# 2DD-17-mk-2_1.net
KiCad netlist of a schematic drawn in EAGLE
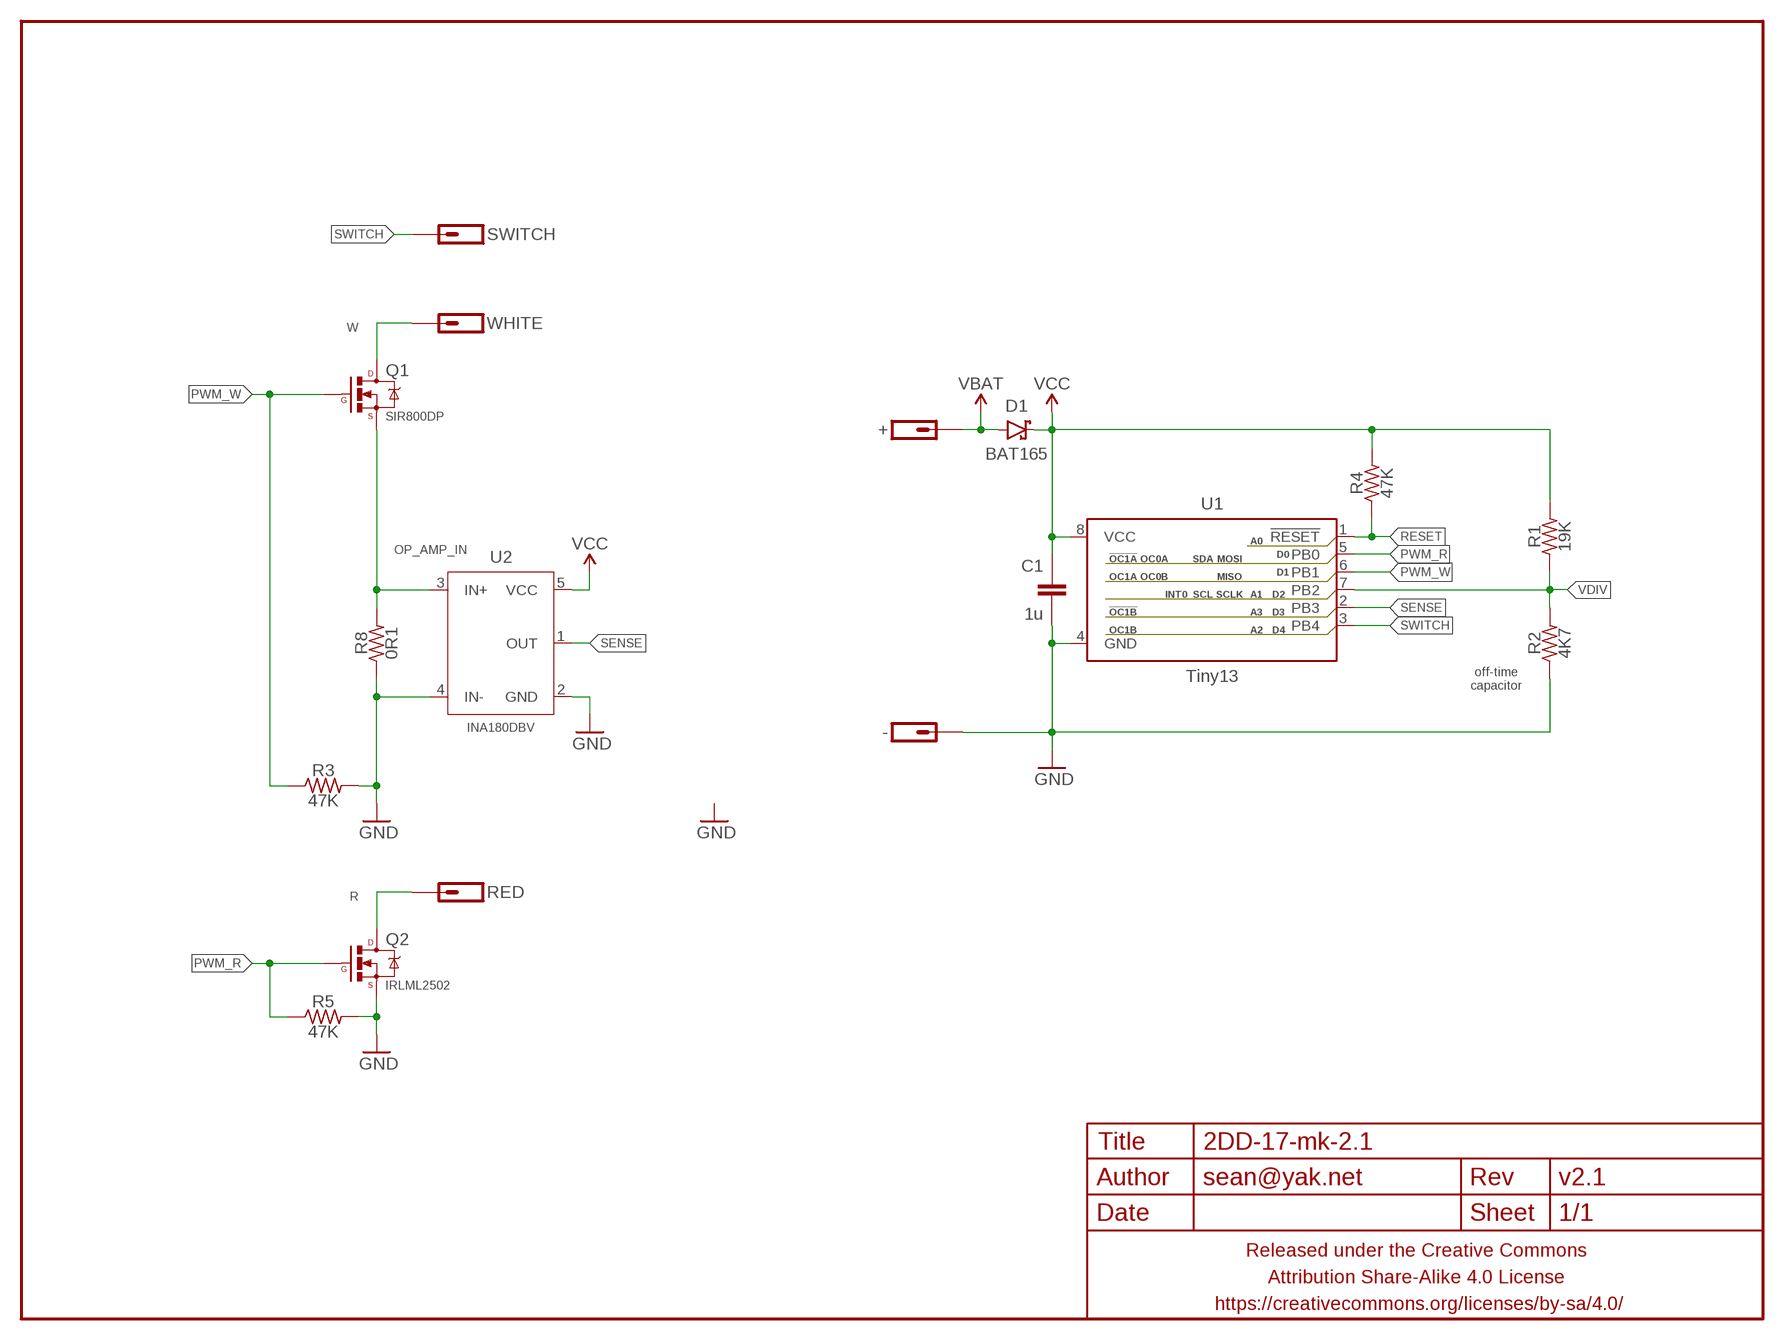
[diagram p0: schematic, sheet 1]

(export (version "E")
  (design (tool "Eeschema 10.0.6"))
  (components
    (comp (ref "+")
      (value "M01PTH-1MM-CIR-NS")
      (footprint "eagle-import:1X01-1MM-CIR-NS")
      (libsource (lib "eagle-import") (part "M01PTH-1MM-CIR-NS"))
    )
    (comp (ref "-")
      (value "M01NOT-A-VIA-NOPE")
      (footprint "eagle-import:1X01_NOSILK_NOSTOP")
      (libsource (lib "eagle-import") (part "M01NOT-A-VIA-NOPE"))
    )
    (comp (ref "C1")
      (value "1u")
      (footprint "eagle-import:C0402")
      (libsource (lib "eagle-import") (part "CAPACITOR-CERAMICC0402"))
    )
    (comp (ref "D1")
      (value "BAT165")
      (footprint "eagle-import:SOD323-SCHOTTKY")
      (libsource (lib "eagle-import") (part "DIODE-SCHOTTKYSOD323"))
    )
    (comp (ref "FRAME1")
      (value "FRAME-LETTERNO_PACKAGE")
      (footprint "eagle-import:DUMMY")
      (fields (field (name "DESIGNER") "sean@yak.net") (field (name "VERSION") "v2.1"))
      (libsource (lib "eagle-import") (part "FRAME-LETTERNO_PACKAGE"))
    )
    (comp (ref "Q1")
      (value "SIR800DP")
      (footprint "eagle-import:POWERPACK-SO-8")
      (libsource (lib "eagle-import") (part "MOSFET-NCHANNELSIR800DP"))
    )
    (comp (ref "Q2")
      (value "IRLML2502")
      (footprint "eagle-import:SOT23-CLOSER")
      (libsource (lib "eagle-import") (part "MOSFET-NCHANNELIRLML2502-SMOL"))
    )
    (comp (ref "R1")
      (value "19K")
      (footprint "eagle-import:R0402")
      (libsource (lib "eagle-import") (part "RESISTORR0402"))
    )
    (comp (ref "R2")
      (value "4K7")
      (footprint "eagle-import:R0402")
      (libsource (lib "eagle-import") (part "RESISTORR0402"))
    )
    (comp (ref "R3")
      (value "47K")
      (footprint "eagle-import:R0402")
      (libsource (lib "eagle-import") (part "RESISTORR0402"))
    )
    (comp (ref "R4")
      (value "47K")
      (footprint "eagle-import:R0402")
      (libsource (lib "eagle-import") (part "RESISTORR0402"))
    )
    (comp (ref "R5")
      (value "47K")
      (footprint "eagle-import:R0402")
      (libsource (lib "eagle-import") (part "RESISTORR0402"))
    )
    (comp (ref "R8")
      (value "0R1")
      (footprint "eagle-import:R1206")
      (libsource (lib "eagle-import") (part "RESISTORR1206"))
    )
    (comp (ref "RED")
      (value "M01SMD-1.25MM-DIA")
      (footprint "eagle-import:1X01-SMD-1.25MM-DIA-NS")
      (libsource (lib "eagle-import") (part "M01SMD-1.25MM-DIA"))
    )
    (comp (ref "SWITCH")
      (value "M01SMD-1.25MM-DIA")
      (footprint "eagle-import:1X01-SMD-1.25MM-DIA-NS")
      (libsource (lib "eagle-import") (part "M01SMD-1.25MM-DIA"))
    )
    (comp (ref "U1")
      (value "Tiny13")
      (footprint "eagle-import:SO08-NARROWER")
      (libsource (lib "eagle-import") (part "ATTINY13SOIC-NARROWPADS"))
    )
    (comp (ref "U2")
      (value "INA180DBV")
      (footprint "eagle-import:SOT23-5")
      (libsource (lib "eagle-import") (part "INA180DBV"))
    )
    (comp (ref "WHITE")
      (value "M01SMD-1.25MM-DIA")
      (footprint "eagle-import:1X01-SMD-1.25MM-DIA-NS")
      (libsource (lib "eagle-import") (part "M01SMD-1.25MM-DIA"))
    )
  )
  (nets
    (net (code "1") (name "/OP_AMP_IN") (class "Default")
      (node (ref "Q1") (pin "1") (pinfunction "S_1") (pintype "passive"))
      (node (ref "Q1") (pin "2") (pinfunction "S_2") (pintype "passive"))
      (node (ref "Q1") (pin "3") (pinfunction "S_3") (pintype "passive"))
      (node (ref "R8") (pin "2") (pinfunction "2_2") (pintype "passive"))
      (node (ref "U2") (pin "3") (pinfunction "IN+_3") (pintype "bidirectional"))
    )
    (net (code "2") (name "/R") (class "Default")
      (node (ref "Q2") (pin "3") (pinfunction "D_3") (pintype "passive"))
      (node (ref "RED") (pin "P$1") (pinfunction "1_P$1") (pintype "passive"))
    )
    (net (code "3") (name "/W") (class "Default")
      (node (ref "Q1") (pin "5678") (pinfunction "D_5678") (pintype "passive"))
      (node (ref "WHITE") (pin "P$1") (pinfunction "1_P$1") (pintype "passive"))
    )
    (net (code "4") (name "GND") (class "Default")
      (node (ref "-") (pin "P$1") (pinfunction "1_P$1") (pintype "passive"))
      (node (ref "C1") (pin "2") (pinfunction "2_2") (pintype "passive"))
      (node (ref "Q2") (pin "2") (pinfunction "S_2") (pintype "passive"))
      (node (ref "R2") (pin "1") (pinfunction "1_1") (pintype "passive"))
      (node (ref "R3") (pin "2") (pinfunction "2_2") (pintype "passive"))
      (node (ref "R5") (pin "2") (pinfunction "2_2") (pintype "passive"))
      (node (ref "R8") (pin "1") (pinfunction "1_1") (pintype "passive"))
      (node (ref "U1") (pin "4") (pinfunction "GND_4") (pintype "bidirectional"))
      (node (ref "U2") (pin "2") (pinfunction "GND_2") (pintype "bidirectional"))
      (node (ref "U2") (pin "4") (pinfunction "IN-_4") (pintype "bidirectional"))
    )
    (net (code "5") (name "PWM_R") (class "Default")
      (node (ref "Q2") (pin "1") (pinfunction "G_1") (pintype "passive"))
      (node (ref "R5") (pin "1") (pinfunction "1_1") (pintype "passive"))
      (node (ref "U1") (pin "5") (pinfunction "PB0_5") (pintype "bidirectional"))
    )
    (net (code "6") (name "PWM_W") (class "Default")
      (node (ref "Q1") (pin "4") (pinfunction "G_4") (pintype "passive"))
      (node (ref "R3") (pin "1") (pinfunction "1_1") (pintype "passive"))
      (node (ref "U1") (pin "6") (pinfunction "PB1_6") (pintype "bidirectional"))
    )
    (net (code "7") (name "RESET") (class "Default")
      (node (ref "R4") (pin "1") (pinfunction "1_1") (pintype "passive"))
      (node (ref "U1") (pin "1") (pinfunction "~{RESET}_1") (pintype "bidirectional"))
    )
    (net (code "8") (name "SENSE") (class "Default")
      (node (ref "U1") (pin "2") (pinfunction "PB3_2") (pintype "bidirectional"))
      (node (ref "U2") (pin "1") (pinfunction "OUT_1") (pintype "bidirectional"))
    )
    (net (code "9") (name "SWITCH") (class "Default")
      (node (ref "SWITCH") (pin "P$1") (pinfunction "1_P$1") (pintype "passive"))
      (node (ref "U1") (pin "3") (pinfunction "PB4_3") (pintype "bidirectional"))
    )
    (net (code "10") (name "VBAT") (class "Default")
      (node (ref "+") (pin "1") (pinfunction "1_1") (pintype "passive"))
      (node (ref "D1") (pin "A") (pinfunction "A_A") (pintype "passive"))
    )
    (net (code "11") (name "VCC") (class "Default")
      (node (ref "C1") (pin "1") (pinfunction "1_1") (pintype "passive"))
      (node (ref "D1") (pin "C") (pinfunction "C_C") (pintype "passive"))
      (node (ref "R1") (pin "2") (pinfunction "2_2") (pintype "passive"))
      (node (ref "R4") (pin "2") (pinfunction "2_2") (pintype "passive"))
      (node (ref "U1") (pin "8") (pinfunction "VCC_8") (pintype "bidirectional"))
      (node (ref "U2") (pin "5") (pinfunction "VCC_5") (pintype "bidirectional"))
    )
    (net (code "12") (name "VDIV") (class "Default")
      (node (ref "R1") (pin "1") (pinfunction "1_1") (pintype "passive"))
      (node (ref "R2") (pin "2") (pinfunction "2_2") (pintype "passive"))
      (node (ref "U1") (pin "7") (pinfunction "PB2_7") (pintype "bidirectional"))
    )
  )
)
